# beagleboard.net
KiCad netlist of a schematic drawn in EAGLE
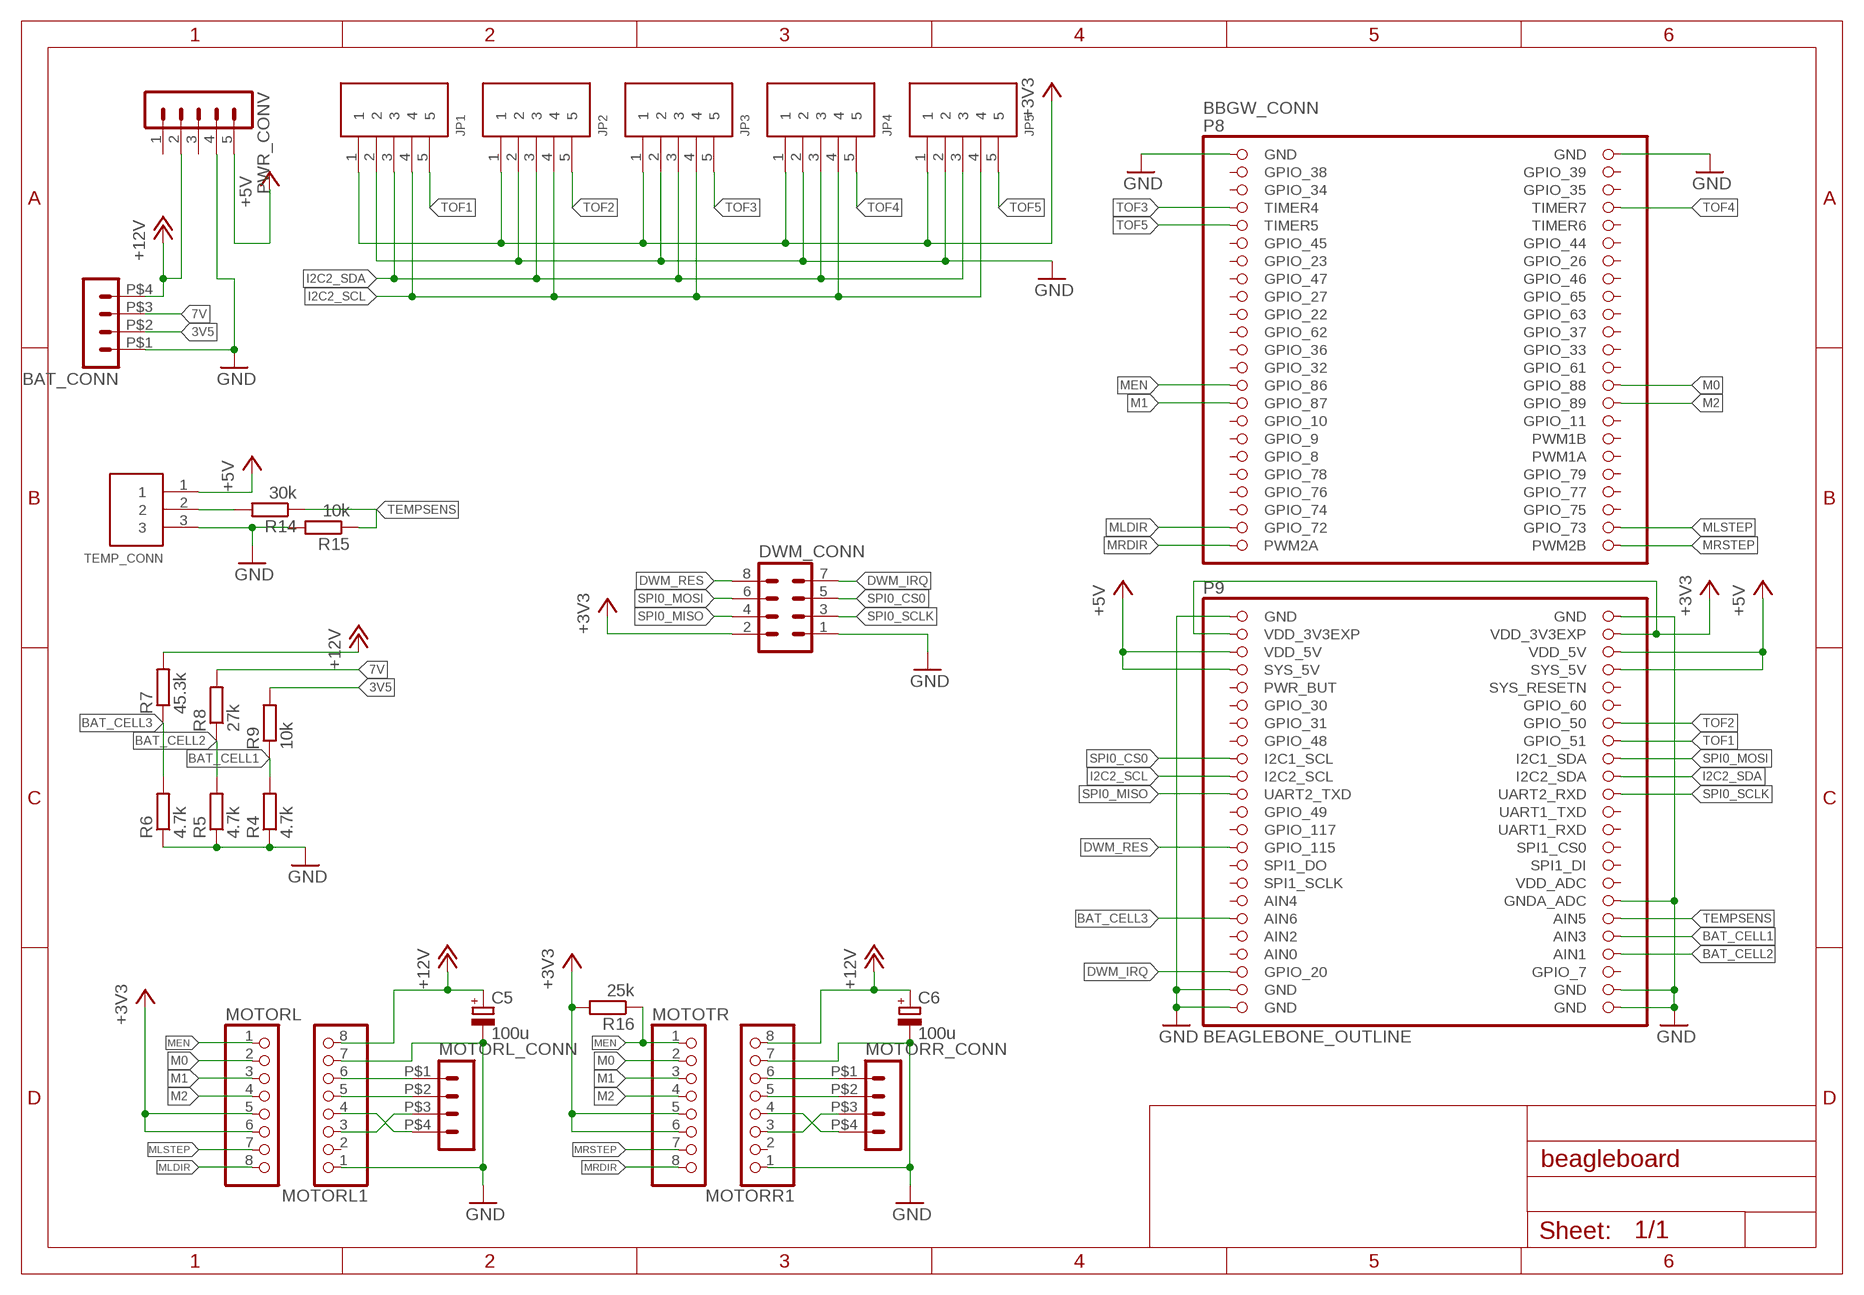
[diagram p0: schematic, sheet 1]

(export (version "E")
  (design (tool "Eeschema 10.0.6"))
  (components
    (comp (ref "BAT_CONN")
      (value "HEADER_POS4_43045-0412")
      (footprint "eagle-import:43045-0412")
      (libsource (lib "eagle-import") (part "HEADER_POS4_?43045-0412"))
    )
    (comp (ref "BBGW_CONN")
      (value "BEAGLEBONE_OUTLINE")
      (footprint "eagle-import:BEAGLEBONE_SHIELD")
      (libsource (lib "eagle-import") (part "BEAGLEBONE_OUTLINE"))
    )
    (comp (ref "C5")
      (value "100u")
      (footprint "eagle-import:153CLV-0405")
      (libsource (lib "eagle-import") (part "CPOL-EU153CLV-0405"))
    )
    (comp (ref "C6")
      (value "100u")
      (footprint "eagle-import:153CLV-0405")
      (libsource (lib "eagle-import") (part "CPOL-EU153CLV-0405"))
    )
    (comp (ref "DWM_CONN")
      (value "MA04-2")
      (footprint "eagle-import:MA04-2")
      (libsource (lib "eagle-import") (part "MA04-2"))
    )
    (comp (ref "JP1")
      (value "5PIN")
      (footprint "eagle-import:B5B-PH-K-S")
      (libsource (lib "eagle-import") (part "5PIN"))
    )
    (comp (ref "JP2")
      (value "5PIN")
      (footprint "eagle-import:B5B-PH-K-S")
      (libsource (lib "eagle-import") (part "5PIN"))
    )
    (comp (ref "JP3")
      (value "5PIN")
      (footprint "eagle-import:B5B-PH-K-S")
      (libsource (lib "eagle-import") (part "5PIN"))
    )
    (comp (ref "JP4")
      (value "5PIN")
      (footprint "eagle-import:B5B-PH-K-S")
      (libsource (lib "eagle-import") (part "5PIN"))
    )
    (comp (ref "JP5")
      (value "5PIN")
      (footprint "eagle-import:B5B-PH-K-S")
      (libsource (lib "eagle-import") (part "5PIN"))
    )
    (comp (ref "MOTORL")
      (value "PINHD-1X8")
      (footprint "eagle-import:1X08")
      (libsource (lib "eagle-import") (part "PINHD-1X8"))
    )
    (comp (ref "MOTORL1")
      (value "PINHD-1X8")
      (footprint "eagle-import:1X08")
      (libsource (lib "eagle-import") (part "PINHD-1X8"))
    )
    (comp (ref "MOTORL_CONN")
      (value "HEADER_POS4_43045-0412")
      (footprint "eagle-import:43045-0412")
      (libsource (lib "eagle-import") (part "HEADER_POS4_?43045-0412"))
    )
    (comp (ref "MOTORR1")
      (value "PINHD-1X8")
      (footprint "eagle-import:1X08")
      (libsource (lib "eagle-import") (part "PINHD-1X8"))
    )
    (comp (ref "MOTORR_CONN")
      (value "HEADER_POS4_43045-0412")
      (footprint "eagle-import:43045-0412")
      (libsource (lib "eagle-import") (part "HEADER_POS4_?43045-0412"))
    )
    (comp (ref "MOTOTR")
      (value "PINHD-1X8")
      (footprint "eagle-import:1X08")
      (libsource (lib "eagle-import") (part "PINHD-1X8"))
    )
    (comp (ref "PWR_CONV")
      (value "MA05-1")
      (footprint "eagle-import:MA05-1")
      (libsource (lib "eagle-import") (part "MA05-1"))
    )
    (comp (ref "R4")
      (value "4.7k")
      (footprint "eagle-import:R0603")
      (libsource (lib "eagle-import") (part "R-EU_R0603"))
    )
    (comp (ref "R5")
      (value "4.7k")
      (footprint "eagle-import:R0603")
      (libsource (lib "eagle-import") (part "R-EU_R0603"))
    )
    (comp (ref "R6")
      (value "4.7k")
      (footprint "eagle-import:R0603")
      (libsource (lib "eagle-import") (part "R-EU_R0603"))
    )
    (comp (ref "R7")
      (value "45.3k")
      (footprint "eagle-import:R0603")
      (libsource (lib "eagle-import") (part "R-EU_R0603"))
    )
    (comp (ref "R8")
      (value "27k")
      (footprint "eagle-import:R0603")
      (libsource (lib "eagle-import") (part "R-EU_R0603"))
    )
    (comp (ref "R9")
      (value "10k")
      (footprint "eagle-import:R0603")
      (libsource (lib "eagle-import") (part "R-EU_R0603"))
    )
    (comp (ref "R14")
      (value "30k")
      (footprint "eagle-import:R0603")
      (libsource (lib "eagle-import") (part "R-EU_R0603"))
    )
    (comp (ref "R15")
      (value "10k")
      (footprint "eagle-import:R0603")
      (libsource (lib "eagle-import") (part "R-EU_R0603"))
    )
    (comp (ref "R16")
      (value "25k")
      (footprint "eagle-import:R0805")
      (libsource (lib "eagle-import") (part "R-EU_R0805"))
    )
    (comp (ref "TEMP_CONN")
      (value "3PIN")
      (footprint "eagle-import:B3B-PH-K-S")
      (libsource (lib "eagle-import") (part "3PIN"))
    )
  )
  (nets
    (net (code "1") (name "+3V3") (class "Default")
      (node (ref "BBGW_CONN") (pin "49") (pinfunction "VDD_3V3EXP_49") (pintype "power_in"))
      (node (ref "BBGW_CONN") (pin "50") (pinfunction "VDD_3V3EXP_50") (pintype "power_in"))
      (node (ref "DWM_CONN") (pin "2") (pinfunction "2_2") (pintype "passive"))
      (node (ref "JP1") (pin "1") (pinfunction "1_1") (pintype "bidirectional"))
      (node (ref "JP2") (pin "1") (pinfunction "1_1") (pintype "bidirectional"))
      (node (ref "JP3") (pin "1") (pinfunction "1_1") (pintype "bidirectional"))
      (node (ref "JP4") (pin "1") (pinfunction "1_1") (pintype "bidirectional"))
      (node (ref "JP5") (pin "1") (pinfunction "1_1") (pintype "bidirectional"))
      (node (ref "MOTORL") (pin "5") (pinfunction "5_5") (pintype "passive"))
      (node (ref "MOTORL") (pin "6") (pinfunction "6_6") (pintype "passive"))
      (node (ref "MOTOTR") (pin "5") (pinfunction "5_5") (pintype "passive"))
      (node (ref "MOTOTR") (pin "6") (pinfunction "6_6") (pintype "passive"))
      (node (ref "R16") (pin "2") (pinfunction "2_2") (pintype "passive"))
    )
    (net (code "2") (name "+5V") (class "Default")
      (node (ref "BBGW_CONN") (pin "51") (pinfunction "VDD_5V_51") (pintype "power_in"))
      (node (ref "BBGW_CONN") (pin "52") (pinfunction "VDD_5V_52") (pintype "power_in"))
      (node (ref "BBGW_CONN") (pin "53") (pinfunction "SYS_5V_53") (pintype "power_in"))
      (node (ref "BBGW_CONN") (pin "54") (pinfunction "SYS_5V_54") (pintype "passive"))
      (node (ref "PWR_CONV") (pin "5") (pinfunction "5_5") (pintype "passive"))
      (node (ref "TEMP_CONN") (pin "1") (pinfunction "1_1") (pintype "bidirectional"))
    )
    (net (code "3") (name "+12V") (class "Default")
      (node (ref "BAT_CONN") (pin "P$4") (pinfunction "4_P$4") (pintype "passive"))
      (node (ref "C5") (pin "+") (pinfunction "+_+") (pintype "passive"))
      (node (ref "C6") (pin "+") (pinfunction "+_+") (pintype "passive"))
      (node (ref "MOTORL1") (pin "8") (pinfunction "8_8") (pintype "passive"))
      (node (ref "MOTORR1") (pin "8") (pinfunction "8_8") (pintype "passive"))
      (node (ref "PWR_CONV") (pin "2") (pinfunction "2_2") (pintype "passive"))
      (node (ref "R7") (pin "2") (pinfunction "2_2") (pintype "passive"))
    )
    (net (code "4") (name "/AIN0") (class "Default")
      (node (ref "BBGW_CONN") (pin "85") (pinfunction "AIN0_85") (pintype "power_in"))
    )
    (net (code "5") (name "3V5") (class "Default")
      (node (ref "BAT_CONN") (pin "P$2") (pinfunction "2_P$2") (pintype "passive"))
      (node (ref "R9") (pin "2") (pinfunction "2_2") (pintype "passive"))
    )
    (net (code "6") (name "7V") (class "Default")
      (node (ref "BAT_CONN") (pin "P$3") (pinfunction "3_P$3") (pintype "passive"))
      (node (ref "R8") (pin "2") (pinfunction "2_2") (pintype "passive"))
    )
    (net (code "7") (name "BAT_CELL1") (class "Default")
      (node (ref "BBGW_CONN") (pin "84") (pinfunction "AIN3_84") (pintype "passive"))
      (node (ref "R4") (pin "2") (pinfunction "2_2") (pintype "passive"))
      (node (ref "R9") (pin "1") (pinfunction "1_1") (pintype "passive"))
    )
    (net (code "8") (name "BAT_CELL2") (class "Default")
      (node (ref "BBGW_CONN") (pin "86") (pinfunction "AIN1_86") (pintype "passive"))
      (node (ref "R5") (pin "2") (pinfunction "2_2") (pintype "passive"))
      (node (ref "R8") (pin "1") (pinfunction "1_1") (pintype "passive"))
    )
    (net (code "9") (name "BAT_CELL3") (class "Default")
      (node (ref "BBGW_CONN") (pin "81") (pinfunction "AIN6_81") (pintype "passive"))
      (node (ref "R6") (pin "2") (pinfunction "2_2") (pintype "passive"))
      (node (ref "R7") (pin "1") (pinfunction "1_1") (pintype "passive"))
    )
    (net (code "10") (name "DWM_IRQ") (class "Default")
      (node (ref "BBGW_CONN") (pin "87") (pinfunction "GPIO_20_87") (pintype "input"))
      (node (ref "DWM_CONN") (pin "7") (pinfunction "7_7") (pintype "passive"))
    )
    (net (code "11") (name "DWM_RES") (class "Default")
      (node (ref "BBGW_CONN") (pin "73") (pinfunction "GPIO_115_73") (pintype "passive"))
      (node (ref "DWM_CONN") (pin "8") (pinfunction "8_8") (pintype "passive"))
    )
    (net (code "12") (name "GND") (class "Default")
      (node (ref "BAT_CONN") (pin "P$1") (pinfunction "1_P$1") (pintype "passive"))
      (node (ref "BBGW_CONN") (pin "1") (pinfunction "GND_1") (pintype "power_in"))
      (node (ref "BBGW_CONN") (pin "2") (pinfunction "GND_2") (pintype "power_in"))
      (node (ref "BBGW_CONN") (pin "47") (pinfunction "GND_47") (pintype "power_in"))
      (node (ref "BBGW_CONN") (pin "48") (pinfunction "GND_48") (pintype "power_in"))
      (node (ref "BBGW_CONN") (pin "80") (pinfunction "GNDA_ADC_80") (pintype "passive"))
      (node (ref "BBGW_CONN") (pin "89") (pinfunction "GND_89") (pintype "power_in"))
      (node (ref "BBGW_CONN") (pin "90") (pinfunction "GND_90") (pintype "power_in"))
      (node (ref "BBGW_CONN") (pin "91") (pinfunction "GND_91") (pintype "power_in"))
      (node (ref "BBGW_CONN") (pin "92") (pinfunction "GND_92") (pintype "power_in"))
      (node (ref "C5") (pin "-") (pinfunction "-_-") (pintype "passive"))
      (node (ref "C6") (pin "-") (pinfunction "-_-") (pintype "passive"))
      (node (ref "DWM_CONN") (pin "1") (pinfunction "1_1") (pintype "passive"))
      (node (ref "JP1") (pin "2") (pinfunction "2_2") (pintype "bidirectional"))
      (node (ref "JP2") (pin "2") (pinfunction "2_2") (pintype "bidirectional"))
      (node (ref "JP3") (pin "2") (pinfunction "2_2") (pintype "bidirectional"))
      (node (ref "JP4") (pin "2") (pinfunction "2_2") (pintype "bidirectional"))
      (node (ref "JP5") (pin "2") (pinfunction "2_2") (pintype "bidirectional"))
      (node (ref "MOTORL1") (pin "1") (pinfunction "1_1") (pintype "passive"))
      (node (ref "MOTORL1") (pin "7") (pinfunction "7_7") (pintype "passive"))
      (node (ref "MOTORR1") (pin "1") (pinfunction "1_1") (pintype "passive"))
      (node (ref "MOTORR1") (pin "7") (pinfunction "7_7") (pintype "passive"))
      (node (ref "PWR_CONV") (pin "4") (pinfunction "4_4") (pintype "passive"))
      (node (ref "R15") (pin "2") (pinfunction "2_2") (pintype "passive"))
      (node (ref "R4") (pin "1") (pinfunction "1_1") (pintype "passive"))
      (node (ref "R5") (pin "1") (pinfunction "1_1") (pintype "passive"))
      (node (ref "R6") (pin "1") (pinfunction "1_1") (pintype "passive"))
      (node (ref "TEMP_CONN") (pin "3") (pinfunction "3_3") (pintype "bidirectional"))
    )
    (net (code "13") (name "I2C2_SCL") (class "Default")
      (node (ref "BBGW_CONN") (pin "65") (pinfunction "I2C2_SCL_65") (pintype "passive"))
      (node (ref "JP1") (pin "4") (pinfunction "4_4") (pintype "bidirectional"))
      (node (ref "JP2") (pin "4") (pinfunction "4_4") (pintype "bidirectional"))
      (node (ref "JP3") (pin "4") (pinfunction "4_4") (pintype "bidirectional"))
      (node (ref "JP4") (pin "4") (pinfunction "4_4") (pintype "bidirectional"))
      (node (ref "JP5") (pin "4") (pinfunction "4_4") (pintype "bidirectional"))
    )
    (net (code "14") (name "I2C2_SDA") (class "Default")
      (node (ref "BBGW_CONN") (pin "66") (pinfunction "I2C2_SDA_66") (pintype "passive"))
      (node (ref "JP1") (pin "3") (pinfunction "3_3") (pintype "bidirectional"))
      (node (ref "JP2") (pin "3") (pinfunction "3_3") (pintype "bidirectional"))
      (node (ref "JP3") (pin "3") (pinfunction "3_3") (pintype "bidirectional"))
      (node (ref "JP4") (pin "3") (pinfunction "3_3") (pintype "bidirectional"))
      (node (ref "JP5") (pin "3") (pinfunction "3_3") (pintype "bidirectional"))
    )
    (net (code "15") (name "M0") (class "Default")
      (node (ref "BBGW_CONN") (pin "28") (pinfunction "GPIO_88_28") (pintype "passive"))
      (node (ref "MOTORL") (pin "2") (pinfunction "2_2") (pintype "passive"))
      (node (ref "MOTOTR") (pin "2") (pinfunction "2_2") (pintype "passive"))
    )
    (net (code "16") (name "M1") (class "Default")
      (node (ref "BBGW_CONN") (pin "29") (pinfunction "GPIO_87_29") (pintype "passive"))
      (node (ref "MOTORL") (pin "3") (pinfunction "3_3") (pintype "passive"))
      (node (ref "MOTOTR") (pin "3") (pinfunction "3_3") (pintype "passive"))
    )
    (net (code "17") (name "M2") (class "Default")
      (node (ref "BBGW_CONN") (pin "30") (pinfunction "GPIO_89_30") (pintype "passive"))
      (node (ref "MOTORL") (pin "4") (pinfunction "4_4") (pintype "passive"))
      (node (ref "MOTOTR") (pin "4") (pinfunction "4_4") (pintype "passive"))
    )
    (net (code "18") (name "MEN") (class "Default")
      (node (ref "BBGW_CONN") (pin "27") (pinfunction "GPIO_86_27") (pintype "passive"))
      (node (ref "MOTORL") (pin "1") (pinfunction "1_1") (pintype "passive"))
      (node (ref "MOTOTR") (pin "1") (pinfunction "1_1") (pintype "passive"))
      (node (ref "R16") (pin "1") (pinfunction "1_1") (pintype "passive"))
    )
    (net (code "19") (name "MLDIR") (class "Default")
      (node (ref "BBGW_CONN") (pin "43") (pinfunction "GPIO_72_43") (pintype "passive"))
      (node (ref "MOTORL") (pin "8") (pinfunction "8_8") (pintype "passive"))
    )
    (net (code "20") (name "MLSTEP") (class "Default")
      (node (ref "BBGW_CONN") (pin "44") (pinfunction "GPIO_73_44") (pintype "passive"))
      (node (ref "MOTORL") (pin "7") (pinfunction "7_7") (pintype "passive"))
    )
    (net (code "21") (name "MRDIR") (class "Default")
      (node (ref "BBGW_CONN") (pin "45") (pinfunction "PWM2A_45") (pintype "passive"))
      (node (ref "MOTOTR") (pin "8") (pinfunction "8_8") (pintype "passive"))
    )
    (net (code "22") (name "MRSTEP") (class "Default")
      (node (ref "BBGW_CONN") (pin "46") (pinfunction "PWM2B_46") (pintype "passive"))
      (node (ref "MOTOTR") (pin "7") (pinfunction "7_7") (pintype "passive"))
    )
    (net (code "23") (name "Net-(MOTORL_CONN-1)") (class "Default")
      (node (ref "MOTORL1") (pin "6") (pinfunction "6_6") (pintype "passive"))
      (node (ref "MOTORL_CONN") (pin "P$1") (pinfunction "1_P$1") (pintype "passive"))
    )
    (net (code "24") (name "Net-(MOTORL_CONN-2)") (class "Default")
      (node (ref "MOTORL1") (pin "5") (pinfunction "5_5") (pintype "passive"))
      (node (ref "MOTORL_CONN") (pin "P$2") (pinfunction "2_P$2") (pintype "passive"))
    )
    (net (code "25") (name "Net-(MOTORL_CONN-3)") (class "Default")
      (node (ref "MOTORL1") (pin "3") (pinfunction "3_3") (pintype "passive"))
      (node (ref "MOTORL_CONN") (pin "P$3") (pinfunction "3_P$3") (pintype "passive"))
    )
    (net (code "26") (name "Net-(MOTORL_CONN-4)") (class "Default")
      (node (ref "MOTORL1") (pin "4") (pinfunction "4_4") (pintype "passive"))
      (node (ref "MOTORL_CONN") (pin "P$4") (pinfunction "4_P$4") (pintype "passive"))
    )
    (net (code "27") (name "Net-(MOTORR_CONN-1)") (class "Default")
      (node (ref "MOTORR1") (pin "6") (pinfunction "6_6") (pintype "passive"))
      (node (ref "MOTORR_CONN") (pin "P$1") (pinfunction "1_P$1") (pintype "passive"))
    )
    (net (code "28") (name "Net-(MOTORR_CONN-2)") (class "Default")
      (node (ref "MOTORR1") (pin "5") (pinfunction "5_5") (pintype "passive"))
      (node (ref "MOTORR_CONN") (pin "P$2") (pinfunction "2_P$2") (pintype "passive"))
    )
    (net (code "29") (name "Net-(MOTORR_CONN-3)") (class "Default")
      (node (ref "MOTORR1") (pin "3") (pinfunction "3_3") (pintype "passive"))
      (node (ref "MOTORR_CONN") (pin "P$3") (pinfunction "3_P$3") (pintype "passive"))
    )
    (net (code "30") (name "Net-(MOTORR_CONN-4)") (class "Default")
      (node (ref "MOTORR1") (pin "4") (pinfunction "4_4") (pintype "passive"))
      (node (ref "MOTORR_CONN") (pin "P$4") (pinfunction "4_P$4") (pintype "passive"))
    )
    (net (code "31") (name "Net-(R14-Pad2)") (class "Default")
      (node (ref "R14") (pin "2") (pinfunction "2_2") (pintype "passive"))
      (node (ref "TEMP_CONN") (pin "2") (pinfunction "2_2") (pintype "bidirectional"))
    )
    (net (code "32") (name "SPI0_CS0") (class "Default")
      (node (ref "BBGW_CONN") (pin "63") (pinfunction "I2C1_SCL_63") (pintype "passive"))
      (node (ref "DWM_CONN") (pin "5") (pinfunction "5_5") (pintype "passive"))
    )
    (net (code "33") (name "SPI0_MISO") (class "Default")
      (node (ref "BBGW_CONN") (pin "67") (pinfunction "UART2_TXD_67") (pintype "passive"))
      (node (ref "DWM_CONN") (pin "4") (pinfunction "4_4") (pintype "passive"))
    )
    (net (code "34") (name "SPI0_MOSI") (class "Default")
      (node (ref "BBGW_CONN") (pin "64") (pinfunction "I2C1_SDA_64") (pintype "passive"))
      (node (ref "DWM_CONN") (pin "6") (pinfunction "6_6") (pintype "passive"))
    )
    (net (code "35") (name "SPI0_SCLK") (class "Default")
      (node (ref "BBGW_CONN") (pin "68") (pinfunction "UART2_RXD_68") (pintype "passive"))
      (node (ref "DWM_CONN") (pin "3") (pinfunction "3_3") (pintype "passive"))
    )
    (net (code "36") (name "TEMPSENS") (class "Default")
      (node (ref "BBGW_CONN") (pin "82") (pinfunction "AIN5_82") (pintype "passive"))
      (node (ref "R14") (pin "1") (pinfunction "1_1") (pintype "passive"))
      (node (ref "R15") (pin "1") (pinfunction "1_1") (pintype "passive"))
    )
    (net (code "37") (name "TOF1") (class "Default")
      (node (ref "BBGW_CONN") (pin "62") (pinfunction "GPIO_51_62") (pintype "passive"))
      (node (ref "JP1") (pin "5") (pinfunction "5_5") (pintype "bidirectional"))
    )
    (net (code "38") (name "TOF2") (class "Default")
      (node (ref "BBGW_CONN") (pin "60") (pinfunction "GPIO_50_60") (pintype "passive"))
      (node (ref "JP2") (pin "5") (pinfunction "5_5") (pintype "bidirectional"))
    )
    (net (code "39") (name "TOF3") (class "Default")
      (node (ref "BBGW_CONN") (pin "7") (pinfunction "TIMER4_7") (pintype "passive"))
      (node (ref "JP3") (pin "5") (pinfunction "5_5") (pintype "bidirectional"))
    )
    (net (code "40") (name "TOF4") (class "Default")
      (node (ref "BBGW_CONN") (pin "8") (pinfunction "TIMER7_8") (pintype "passive"))
      (node (ref "JP4") (pin "5") (pinfunction "5_5") (pintype "bidirectional"))
    )
    (net (code "41") (name "TOF5") (class "Default")
      (node (ref "BBGW_CONN") (pin "9") (pinfunction "TIMER5_9") (pintype "passive"))
      (node (ref "JP5") (pin "5") (pinfunction "5_5") (pintype "bidirectional"))
    )
    (net (code "42") (name "unconnected-(BBGW_CONN-AIN2-Pad83)") (class "Default")
      (node (ref "BBGW_CONN") (pin "83") (pinfunction "AIN2_83") (pintype "passive"))
    )
    (net (code "43") (name "unconnected-(BBGW_CONN-AIN4-Pad79)") (class "Default")
      (node (ref "BBGW_CONN") (pin "79") (pinfunction "AIN4_79") (pintype "passive"))
    )
    (net (code "44") (name "unconnected-(BBGW_CONN-GPIO_7-Pad88)") (class "Default")
      (node (ref "BBGW_CONN") (pin "88") (pinfunction "GPIO_7_88") (pintype "passive"))
    )
    (net (code "45") (name "unconnected-(BBGW_CONN-GPIO_8-Pad35)") (class "Default")
      (node (ref "BBGW_CONN") (pin "35") (pinfunction "GPIO_8_35") (pintype "passive"))
    )
    (net (code "46") (name "unconnected-(BBGW_CONN-GPIO_9-Pad33)") (class "Default")
      (node (ref "BBGW_CONN") (pin "33") (pinfunction "GPIO_9_33") (pintype "passive"))
    )
    (net (code "47") (name "unconnected-(BBGW_CONN-GPIO_10-Pad31)") (class "Default")
      (node (ref "BBGW_CONN") (pin "31") (pinfunction "GPIO_10_31") (pintype "passive"))
    )
    (net (code "48") (name "unconnected-(BBGW_CONN-GPIO_11-Pad32)") (class "Default")
      (node (ref "BBGW_CONN") (pin "32") (pinfunction "GPIO_11_32") (pintype "passive"))
    )
    (net (code "49") (name "unconnected-(BBGW_CONN-GPIO_22-Pad19)") (class "Default")
      (node (ref "BBGW_CONN") (pin "19") (pinfunction "GPIO_22_19") (pintype "passive"))
    )
    (net (code "50") (name "unconnected-(BBGW_CONN-GPIO_23-Pad13)") (class "Default")
      (node (ref "BBGW_CONN") (pin "13") (pinfunction "GPIO_23_13") (pintype "passive"))
    )
    (net (code "51") (name "unconnected-(BBGW_CONN-GPIO_26-Pad14)") (class "Default")
      (node (ref "BBGW_CONN") (pin "14") (pinfunction "GPIO_26_14") (pintype "passive"))
    )
    (net (code "52") (name "unconnected-(BBGW_CONN-GPIO_27-Pad17)") (class "Default")
      (node (ref "BBGW_CONN") (pin "17") (pinfunction "GPIO_27_17") (pintype "passive"))
    )
    (net (code "53") (name "unconnected-(BBGW_CONN-GPIO_30-Pad57)") (class "Default")
      (node (ref "BBGW_CONN") (pin "57") (pinfunction "GPIO_30_57") (pintype "passive"))
    )
    (net (code "54") (name "unconnected-(BBGW_CONN-GPIO_31-Pad59)") (class "Default")
      (node (ref "BBGW_CONN") (pin "59") (pinfunction "GPIO_31_59") (pintype "passive"))
    )
    (net (code "55") (name "unconnected-(BBGW_CONN-GPIO_32-Pad25)") (class "Default")
      (node (ref "BBGW_CONN") (pin "25") (pinfunction "GPIO_32_25") (pintype "passive"))
    )
    (net (code "56") (name "unconnected-(BBGW_CONN-GPIO_33-Pad24)") (class "Default")
      (node (ref "BBGW_CONN") (pin "24") (pinfunction "GPIO_33_24") (pintype "passive"))
    )
    (net (code "57") (name "unconnected-(BBGW_CONN-GPIO_34-Pad5)") (class "Default")
      (node (ref "BBGW_CONN") (pin "5") (pinfunction "GPIO_34_5") (pintype "passive"))
    )
    (net (code "58") (name "unconnected-(BBGW_CONN-GPIO_35-Pad6)") (class "Default")
      (node (ref "BBGW_CONN") (pin "6") (pinfunction "GPIO_35_6") (pintype "passive"))
    )
    (net (code "59") (name "unconnected-(BBGW_CONN-GPIO_36-Pad23)") (class "Default")
      (node (ref "BBGW_CONN") (pin "23") (pinfunction "GPIO_36_23") (pintype "passive"))
    )
    (net (code "60") (name "unconnected-(BBGW_CONN-GPIO_37-Pad22)") (class "Default")
      (node (ref "BBGW_CONN") (pin "22") (pinfunction "GPIO_37_22") (pintype "passive"))
    )
    (net (code "61") (name "unconnected-(BBGW_CONN-GPIO_38-Pad3)") (class "Default")
      (node (ref "BBGW_CONN") (pin "3") (pinfunction "GPIO_38_3") (pintype "passive"))
    )
    (net (code "62") (name "unconnected-(BBGW_CONN-GPIO_39-Pad4)") (class "Default")
      (node (ref "BBGW_CONN") (pin "4") (pinfunction "GPIO_39_4") (pintype "passive"))
    )
    (net (code "63") (name "unconnected-(BBGW_CONN-GPIO_44-Pad12)") (class "Default")
      (node (ref "BBGW_CONN") (pin "12") (pinfunction "GPIO_44_12") (pintype "passive"))
    )
    (net (code "64") (name "unconnected-(BBGW_CONN-GPIO_45-Pad11)") (class "Default")
      (node (ref "BBGW_CONN") (pin "11") (pinfunction "GPIO_45_11") (pintype "passive"))
    )
    (net (code "65") (name "unconnected-(BBGW_CONN-GPIO_46-Pad16)") (class "Default")
      (node (ref "BBGW_CONN") (pin "16") (pinfunction "GPIO_46_16") (pintype "passive"))
    )
    (net (code "66") (name "unconnected-(BBGW_CONN-GPIO_47-Pad15)") (class "Default")
      (node (ref "BBGW_CONN") (pin "15") (pinfunction "GPIO_47_15") (pintype "passive"))
    )
    (net (code "67") (name "unconnected-(BBGW_CONN-GPIO_48-Pad61)") (class "Default")
      (node (ref "BBGW_CONN") (pin "61") (pinfunction "GPIO_48_61") (pintype "passive"))
    )
    (net (code "68") (name "unconnected-(BBGW_CONN-GPIO_49-Pad69)") (class "Default")
      (node (ref "BBGW_CONN") (pin "69") (pinfunction "GPIO_49_69") (pintype "passive"))
    )
    (net (code "69") (name "unconnected-(BBGW_CONN-GPIO_60-Pad58)") (class "Default")
      (node (ref "BBGW_CONN") (pin "58") (pinfunction "GPIO_60_58") (pintype "passive"))
    )
    (net (code "70") (name "unconnected-(BBGW_CONN-GPIO_61-Pad26)") (class "Default")
      (node (ref "BBGW_CONN") (pin "26") (pinfunction "GPIO_61_26") (pintype "passive"))
    )
    (net (code "71") (name "unconnected-(BBGW_CONN-GPIO_62-Pad21)") (class "Default")
      (node (ref "BBGW_CONN") (pin "21") (pinfunction "GPIO_62_21") (pintype "passive"))
    )
    (net (code "72") (name "unconnected-(BBGW_CONN-GPIO_63-Pad20)") (class "Default")
      (node (ref "BBGW_CONN") (pin "20") (pinfunction "GPIO_63_20") (pintype "passive"))
    )
    (net (code "73") (name "unconnected-(BBGW_CONN-GPIO_65-Pad18)") (class "Default")
      (node (ref "BBGW_CONN") (pin "18") (pinfunction "GPIO_65_18") (pintype "passive"))
    )
    (net (code "74") (name "unconnected-(BBGW_CONN-GPIO_74-Pad41)") (class "Default")
      (node (ref "BBGW_CONN") (pin "41") (pinfunction "GPIO_74_41") (pintype "passive"))
    )
    (net (code "75") (name "unconnected-(BBGW_CONN-GPIO_75-Pad42)") (class "Default")
      (node (ref "BBGW_CONN") (pin "42") (pinfunction "GPIO_75_42") (pintype "passive"))
    )
    (net (code "76") (name "unconnected-(BBGW_CONN-GPIO_76-Pad39)") (class "Default")
      (node (ref "BBGW_CONN") (pin "39") (pinfunction "GPIO_76_39") (pintype "passive"))
    )
    (net (code "77") (name "unconnected-(BBGW_CONN-GPIO_77-Pad40)") (class "Default")
      (node (ref "BBGW_CONN") (pin "40") (pinfunction "GPIO_77_40") (pintype "passive"))
    )
    (net (code "78") (name "unconnected-(BBGW_CONN-GPIO_78-Pad37)") (class "Default")
      (node (ref "BBGW_CONN") (pin "37") (pinfunction "GPIO_78_37") (pintype "passive"))
    )
    (net (code "79") (name "unconnected-(BBGW_CONN-GPIO_79-Pad38)") (class "Default")
      (node (ref "BBGW_CONN") (pin "38") (pinfunction "GPIO_79_38") (pintype "passive"))
    )
    (net (code "80") (name "unconnected-(BBGW_CONN-GPIO_117-Pad71)") (class "Default")
      (node (ref "BBGW_CONN") (pin "71") (pinfunction "GPIO_117_71") (pintype "passive"))
    )
    (net (code "81") (name "unconnected-(BBGW_CONN-PWM1A-Pad36)") (class "Default")
      (node (ref "BBGW_CONN") (pin "36") (pinfunction "PWM1A_36") (pintype "passive"))
    )
    (net (code "82") (name "unconnected-(BBGW_CONN-PWM1B-Pad34)") (class "Default")
      (node (ref "BBGW_CONN") (pin "34") (pinfunction "PWM1B_34") (pintype "passive"))
    )
    (net (code "83") (name "unconnected-(BBGW_CONN-PWR_BUT-Pad55)") (class "Default")
      (node (ref "BBGW_CONN") (pin "55") (pinfunction "PWR_BUT_55") (pintype "passive"))
    )
    (net (code "84") (name "unconnected-(BBGW_CONN-SPI1_CS0-Pad74)") (class "Default")
      (node (ref "BBGW_CONN") (pin "74") (pinfunction "SPI1_CS0_74") (pintype "passive"))
    )
    (net (code "85") (name "unconnected-(BBGW_CONN-SPI1_DI-Pad76)") (class "Default")
      (node (ref "BBGW_CONN") (pin "76") (pinfunction "SPI1_DI_76") (pintype "passive"))
    )
    (net (code "86") (name "unconnected-(BBGW_CONN-SPI1_DO-Pad75)") (class "Default")
      (node (ref "BBGW_CONN") (pin "75") (pinfunction "SPI1_DO_75") (pintype "passive"))
    )
    (net (code "87") (name "unconnected-(BBGW_CONN-SPI1_SCLK-Pad77)") (class "Default")
      (node (ref "BBGW_CONN") (pin "77") (pinfunction "SPI1_SCLK_77") (pintype "passive"))
    )
    (net (code "88") (name "unconnected-(BBGW_CONN-SYS_RESETN-Pad56)") (class "Default")
      (node (ref "BBGW_CONN") (pin "56") (pinfunction "SYS_RESETN_56") (pintype "passive"))
    )
    (net (code "89") (name "unconnected-(BBGW_CONN-TIMER6-Pad10)") (class "Default")
      (node (ref "BBGW_CONN") (pin "10") (pinfunction "TIMER6_10") (pintype "passive"))
    )
    (net (code "90") (name "unconnected-(BBGW_CONN-UART1_RXD-Pad72)") (class "Default")
      (node (ref "BBGW_CONN") (pin "72") (pinfunction "UART1_RXD_72") (pintype "passive"))
    )
    (net (code "91") (name "unconnected-(BBGW_CONN-UART1_TXD-Pad70)") (class "Default")
      (node (ref "BBGW_CONN") (pin "70") (pinfunction "UART1_TXD_70") (pintype "passive"))
    )
    (net (code "92") (name "unconnected-(BBGW_CONN-VDD_ADC-Pad78)") (class "Default")
      (node (ref "BBGW_CONN") (pin "78") (pinfunction "VDD_ADC_78") (pintype "passive"))
    )
    (net (code "93") (name "unconnected-(MOTORL1-Pad2)") (class "Default")
      (node (ref "MOTORL1") (pin "2") (pinfunction "2_2") (pintype "passive"))
    )
    (net (code "94") (name "unconnected-(MOTORR1-Pad2)") (class "Default")
      (node (ref "MOTORR1") (pin "2") (pinfunction "2_2") (pintype "passive"))
    )
    (net (code "95") (name "unconnected-(PWR_CONV-Pad1)") (class "Default")
      (node (ref "PWR_CONV") (pin "1") (pinfunction "1_1") (pintype "passive"))
    )
    (net (code "96") (name "unconnected-(PWR_CONV-Pad3)") (class "Default")
      (node (ref "PWR_CONV") (pin "3") (pinfunction "3_3") (pintype "passive"))
    )
  )
)
